# design.net
KiCad netlist of a schematic drawn in Altium Designer
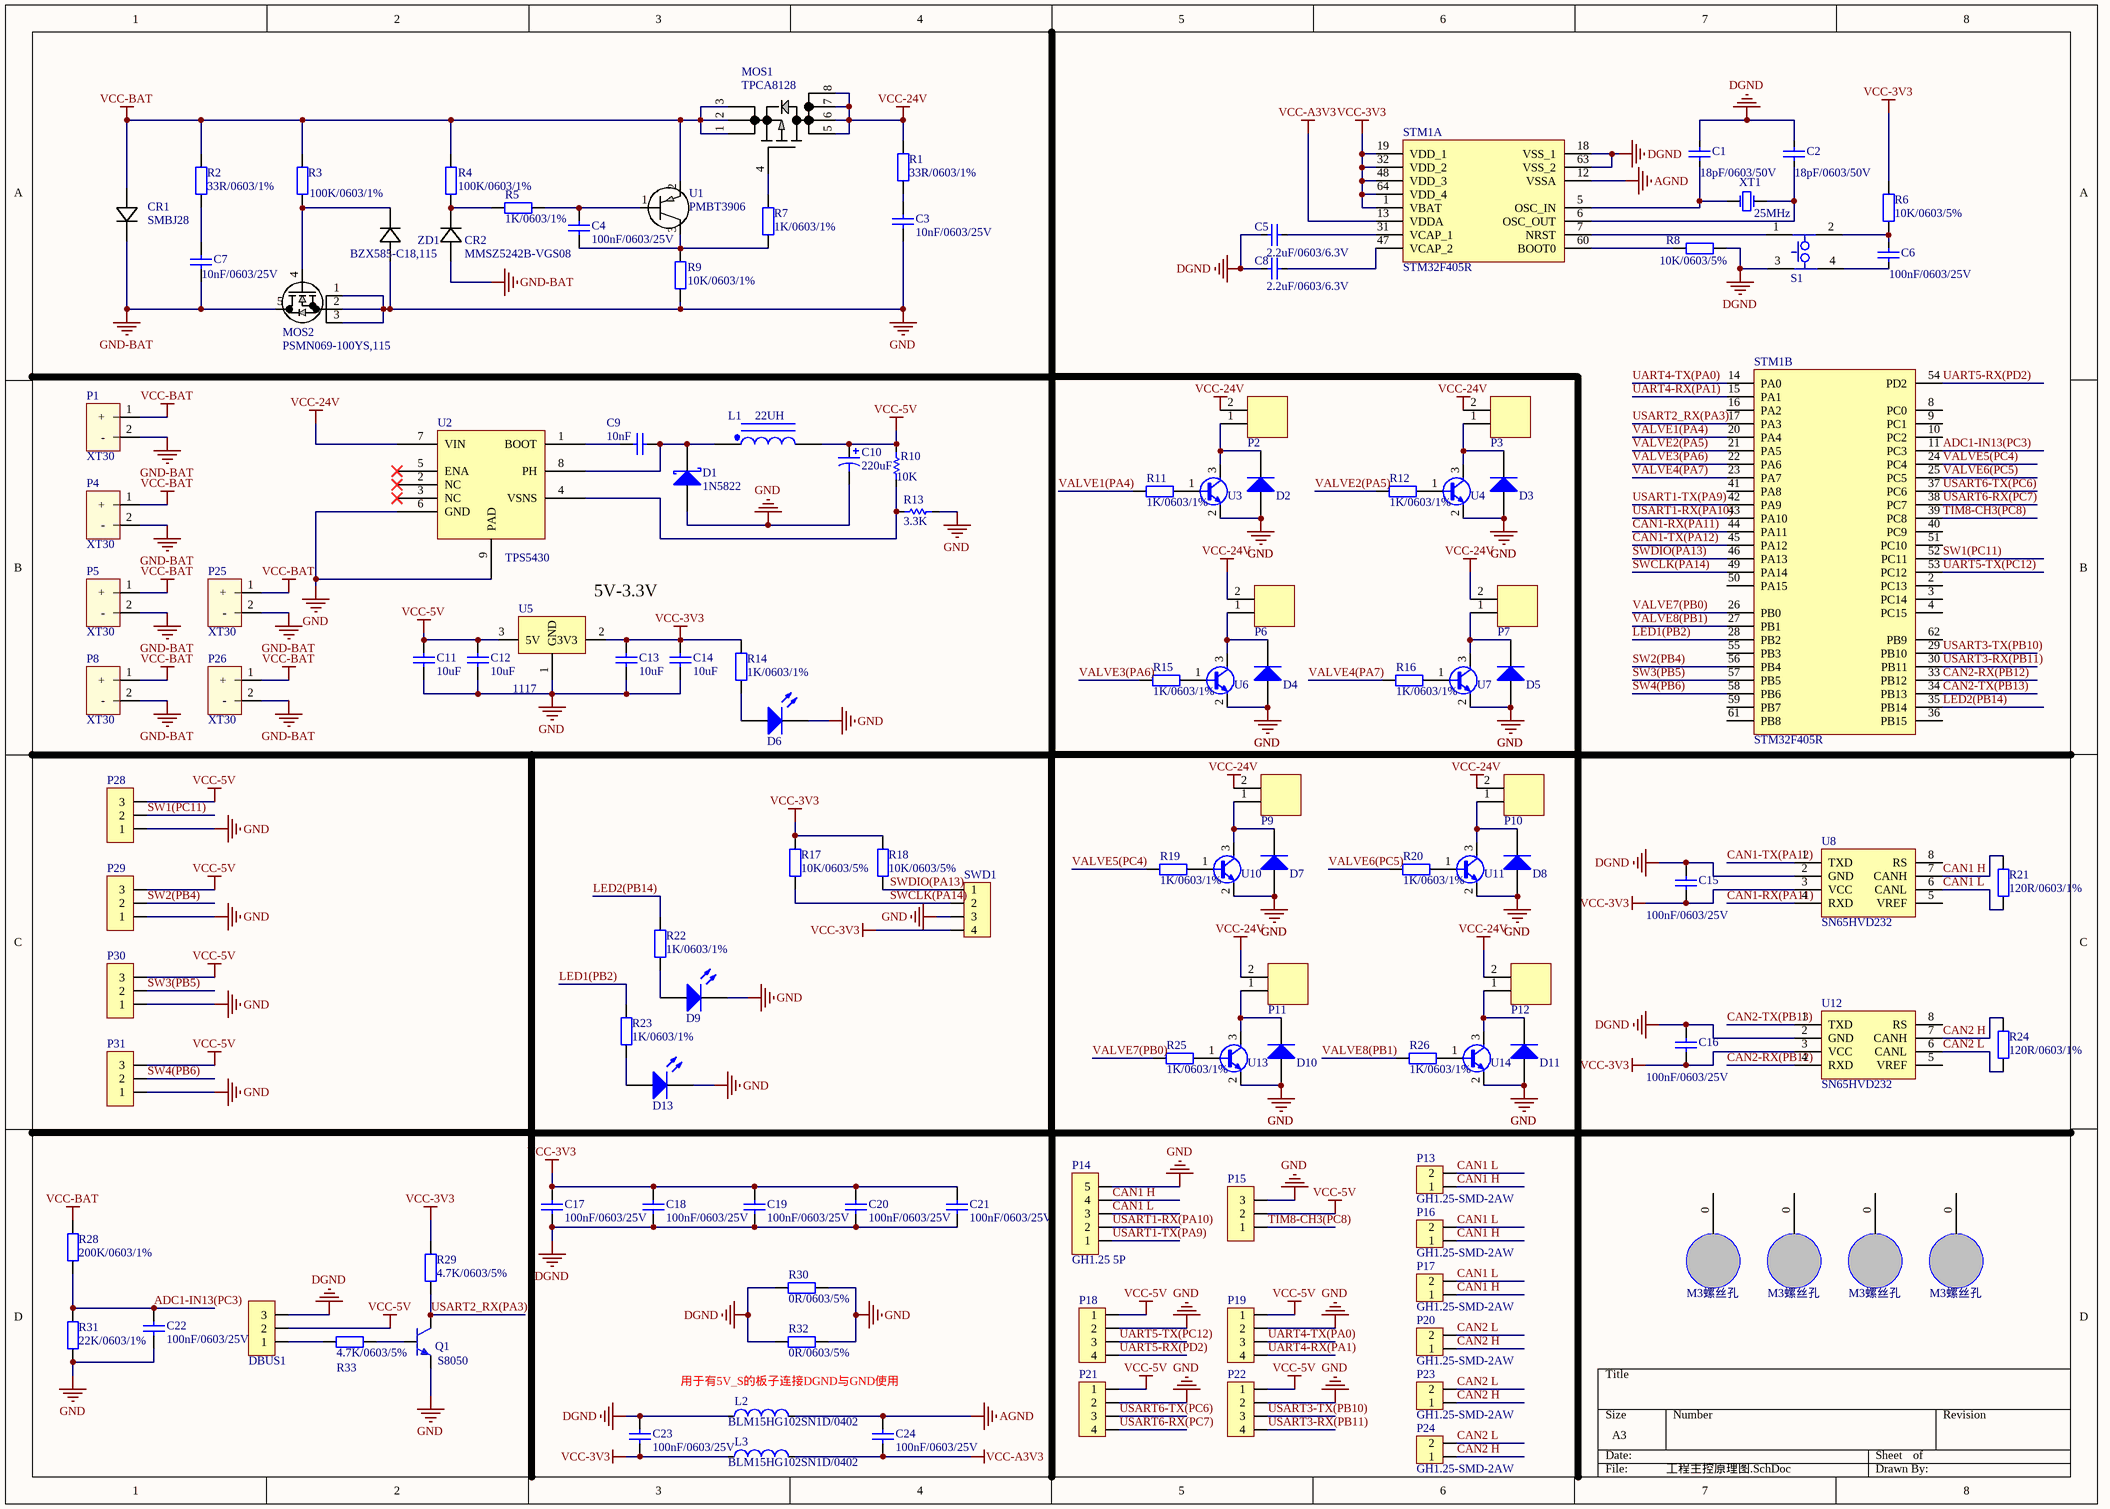
[diagram p0: 工程主控原理图.SchDoc]

(export (version "E")
  (design (tool "Eeschema 10.0.6"))
  (components
    (comp (ref "C1")
      (value "18pF/0603/50V")
      (footprint "C-SMD-0603")
      (description "Capacitor")
      (fields (field (name "Comment") "18pF"))
      (libsource (lib "SCH_Passive") (part "Cap_0402"))
    )
    (comp (ref "C2")
      (value "18pF/0603/50V")
      (footprint "C-SMD-0603")
      (description "Capacitor")
      (fields (field (name "Comment") "18pF"))
      (libsource (lib "SCH_Passive") (part "Cap_0402"))
    )
    (comp (ref "C3")
      (value "10nF/0603/25V")
      (footprint "C-SMD-0603")
      (description "贴片电容")
      (fields (field (name "Comment") "10nF") (field (name "PUBLISHER") "Altium Limited"))
      (libsource (lib "三代主控板原理图库") (part "Cap"))
    )
    (comp (ref "C4")
      (value "100nF/0603/25V")
      (footprint "C-SMD-0603")
      (description "贴片电容")
      (fields (field (name "Comment") "100nF") (field (name "PUBLISHER") "Altium Limited"))
      (libsource (lib "三代主控板原理图库") (part "Cap"))
    )
    (comp (ref "C5")
      (value "2.2uF/0603/6.3V")
      (footprint "C-SMD-0603")
      (description "Capacitor")
      (fields (field (name "Comment") "2.2uF"))
      (libsource (lib "SCH_Passive") (part "Cap_0402"))
    )
    (comp (ref "C6")
      (value "100nF/0603/25V")
      (footprint "C-SMD-0603")
      (description "Capacitor")
      (fields (field (name "Comment") "100nF"))
      (libsource (lib "SCH_Passive") (part "Cap_0402"))
    )
    (comp (ref "C7")
      (value "10nF/0603/25V")
      (footprint "C-SMD-0603")
      (description "贴片电容")
      (fields (field (name "Comment") "10nF") (field (name "PUBLISHER") "Altium Limited"))
      (libsource (lib "三代主控板原理图库") (part "Cap"))
    )
    (comp (ref "C8")
      (value "2.2uF/0603/6.3V")
      (footprint "C-SMD-0603")
      (description "Capacitor")
      (fields (field (name "Comment") "2.2uF"))
      (libsource (lib "SCH_Passive") (part "Cap_0402"))
    )
    (comp (ref "C9")
      (value "10nF")
      (footprint "C-SMD-0603")
      (description "无极性电容")
      (fields (field (name "PUBLISHER") "Altium Limited"))
      (libsource (lib "Devices") (part "Cap"))
    )
    (comp (ref "C10")
      (value "220uF")
      (footprint "TCAP7343")
      (description "Polarized Capacitor (Radial)")
      (fields (field (name "PUBLISHER") "Altium Limited"))
      (libsource (lib "Miscellaneous Devices") (part "Cap Pol1"))
    )
    (comp (ref "C11")
      (value "10uF")
      (footprint "C-SMD-0603")
      (description "无极性电容")
      (fields (field (name "PUBLISHER") "Altium Limited"))
      (libsource (lib "Devices") (part "Cap"))
    )
    (comp (ref "C12")
      (value "10uF")
      (footprint "C-SMD-0603")
      (description "无极性电容")
      (fields (field (name "PUBLISHER") "Altium Limited"))
      (libsource (lib "Devices") (part "Cap"))
    )
    (comp (ref "C13")
      (value "10uF")
      (footprint "C-SMD-0603")
      (description "无极性电容")
      (fields (field (name "PUBLISHER") "Altium Limited"))
      (libsource (lib "Devices") (part "Cap"))
    )
    (comp (ref "C14")
      (value "10uF")
      (footprint "C-SMD-0603")
      (description "无极性电容")
      (fields (field (name "PUBLISHER") "Altium Limited"))
      (libsource (lib "Devices") (part "Cap"))
    )
    (comp (ref "C15")
      (value "100nF/0603/25V")
      (footprint "C-SMD-0603")
      (description "贴片电容")
      (fields (field (name "Comment") "100NF") (field (name "PUBLISHER") "Altium Limited"))
      (libsource (lib "三代主控板原理图库") (part "Cap"))
    )
    (comp (ref "C16")
      (value "100nF/0603/25V")
      (footprint "C-SMD-0603")
      (description "贴片电容")
      (fields (field (name "Comment") "100NF") (field (name "PUBLISHER") "Altium Limited"))
      (libsource (lib "三代主控板原理图库") (part "Cap"))
    )
    (comp (ref "C17")
      (value "100nF/0603/25V")
      (footprint "C-SMD-0603")
      (description "贴片电容")
      (fields (field (name "Comment") "100nF") (field (name "PUBLISHER") "Altium Limited"))
      (libsource (lib "三代主控板原理图库") (part "Cap"))
    )
    (comp (ref "C18")
      (value "100nF/0603/25V")
      (footprint "C-SMD-0603")
      (description "贴片电容")
      (fields (field (name "Comment") "100nF") (field (name "PUBLISHER") "Altium Limited"))
      (libsource (lib "三代主控板原理图库") (part "Cap"))
    )
    (comp (ref "C19")
      (value "100nF/0603/25V")
      (footprint "C-SMD-0603")
      (description "贴片电容")
      (fields (field (name "Comment") "100nF") (field (name "PUBLISHER") "Altium Limited"))
      (libsource (lib "三代主控板原理图库") (part "Cap"))
    )
    (comp (ref "C20")
      (value "100nF/0603/25V")
      (footprint "C-SMD-0603")
      (description "贴片电容")
      (fields (field (name "Comment") "100nF") (field (name "PUBLISHER") "Altium Limited"))
      (libsource (lib "三代主控板原理图库") (part "Cap"))
    )
    (comp (ref "C21")
      (value "100nF/0603/25V")
      (footprint "C-SMD-0603")
      (description "贴片电容")
      (fields (field (name "Comment") "100nF") (field (name "PUBLISHER") "Altium Limited"))
      (libsource (lib "三代主控板原理图库") (part "Cap"))
    )
    (comp (ref "C22")
      (value "100nF/0603/25V")
      (footprint "C-SMD-0603")
      (description "贴片电容")
      (fields (field (name "Comment") "100nF") (field (name "PUBLISHER") "Altium Limited"))
      (libsource (lib "三代主控板原理图库") (part "Cap"))
    )
    (comp (ref "C23")
      (value "100nF/0603/25V")
      (footprint "C-SMD-0603")
      (description "贴片电容")
      (fields (field (name "Comment") "100nF") (field (name "PUBLISHER") "Altium Limited"))
      (libsource (lib "三代主控板原理图库") (part "Cap"))
    )
    (comp (ref "C24")
      (value "100nF/0603/25V")
      (footprint "C-SMD-0603")
      (description "贴片电容")
      (fields (field (name "Comment") "100nF") (field (name "PUBLISHER") "Altium Limited"))
      (libsource (lib "三代主控板原理图库") (part "Cap"))
    )
    (comp (ref "CR1")
      (value "SMBJ28")
      (footprint "SMBJSeries_LTF")
      (description "No Description Available")
      (fields
        (field (name "MANUFACTURER_PART_NUMBER") "SMBJ10")
        (field (name "COPYRIGHT") "Copyright (C) 2018 Accelerated Designs. All rights reserved")
      )
      (libsource (lib "SMBJ") (part "SMBJ10"))
    )
    (comp (ref "CR2")
      (value "MMSZ5242B-VGS08")
      (footprint "SOD123_MMS")
      (description "No Description Available")
      (fields (field (name "COPYRIGHT") "Copyright (C) 2018 Accelerated Designs. All rights reserved"))
      (libsource (lib "mmsz") (part "MMSZ5242B-VGS08"))
    )
    (comp (ref "D1")
      (value "1N5822")
      (footprint "SS34")
      (description "Schottky Diode")
      (fields (field (name "PUBLISHER") "Altium Limited"))
      (libsource (lib "Miscellaneous Devices") (part "D Schottky"))
    )
    (comp (ref "D2")
      (value "Diode_SS34")
      (footprint "SS34")
      (description "肖特基二极管")
      (libsource (lib "SHAWN") (part "Diode_SS34"))
    )
    (comp (ref "D3")
      (value "Diode_SS34")
      (footprint "SS34")
      (description "肖特基二极管")
      (libsource (lib "SHAWN") (part "Diode_SS34"))
    )
    (comp (ref "D4")
      (value "Diode_SS34")
      (footprint "SS34")
      (description "肖特基二极管")
      (libsource (lib "SHAWN") (part "Diode_SS34"))
    )
    (comp (ref "D5")
      (value "Diode_SS34")
      (footprint "SS34")
      (description "肖特基二极管")
      (libsource (lib "SHAWN") (part "Diode_SS34"))
    )
    (comp (ref "D6")
      (value "LED0")
      (footprint "LED-0603")
      (description "发光二极管")
      (fields (field (name "PUBLISHER") "Altium Limited"))
      (libsource (lib "Devices") (part "LED0"))
    )
    (comp (ref "D7")
      (value "Diode_SS34")
      (footprint "SS34")
      (description "肖特基二极管")
      (libsource (lib "SHAWN") (part "Diode_SS34"))
    )
    (comp (ref "D8")
      (value "Diode_SS34")
      (footprint "SS34")
      (description "肖特基二极管")
      (libsource (lib "SHAWN") (part "Diode_SS34"))
    )
    (comp (ref "D9")
      (value "LED0")
      (footprint "LED-0603")
      (description "发光二极管")
      (fields (field (name "PUBLISHER") "Altium Limited"))
      (libsource (lib "Devices") (part "LED0"))
    )
    (comp (ref "D10")
      (value "Diode_SS34")
      (footprint "SS34")
      (description "肖特基二极管")
      (libsource (lib "SHAWN") (part "Diode_SS34"))
    )
    (comp (ref "D11")
      (value "Diode_SS34")
      (footprint "SS34")
      (description "肖特基二极管")
      (libsource (lib "SHAWN") (part "Diode_SS34"))
    )
    (comp (ref "D13")
      (value "LED0")
      (footprint "LED-0603")
      (description "发光二极管")
      (fields (field (name "PUBLISHER") "Altium Limited"))
      (libsource (lib "Devices") (part "LED0"))
    )
    (comp (ref "DBUS1")
      (value "Header 3")
      (footprint "HDR1x3")
      (description "Header")
      (fields (field (name "PUBLISHER") "Altium Limited"))
      (libsource (lib "排针排母") (part "Header 3"))
    )
    (comp (ref "L1")
      (value "22UH")
      (footprint "L-7070")
      (description "Magnetic-Core Inductor with Winding Polarity Marking")
      (fields (field (name "PUBLISHER") "Altium Limited"))
      (libsource (lib "Miscellaneous Devices") (part "Inductor Iron Dot"))
    )
    (comp (ref "L2")
      (value "BLM15HG102SN1D/0402")
      (footprint "l-SMD-0402")
      (description "Inductor")
      (fields (field (name "Comment") "BLM15HG102SN1D"))
      (libsource (lib "三代主控板原理图库") (part "BLM15HG102SN1D/0402"))
    )
    (comp (ref "L3")
      (value "BLM15HG102SN1D/0402")
      (footprint "l-SMD-0402")
      (description "Inductor")
      (fields (field (name "Comment") "BLM15HG102SN1D"))
      (libsource (lib "三代主控板原理图库") (part "BLM15HG102SN1D/0402"))
    )
    (comp (ref "M1") (value "M3螺丝孔") (footprint "M3螺丝") (libsource (lib "My_SCHLib") (part "M3螺丝孔")))
    (comp (ref "M2") (value "M3螺丝孔") (footprint "M3螺丝") (libsource (lib "My_SCHLib") (part "M3螺丝孔")))
    (comp (ref "M3") (value "M3螺丝孔") (footprint "M3螺丝") (libsource (lib "My_SCHLib") (part "M3螺丝孔")))
    (comp (ref "M4") (value "M3螺丝孔") (footprint "M3螺丝") (libsource (lib "My_SCHLib") (part "M3螺丝孔")))
    (comp (ref "MOS1")
      (value "TPCA8128")
      (footprint "SOP Advance_TOS")
      (description "No Description Available")
      (fields (field (name "COPYRIGHT") "Copyright (C) 2018 Accelerated Designs. All rights reserved"))
      (libsource (lib "TPCA8122") (part "TPCA8128"))
    )
    (comp (ref "MOS2")
      (value "PSMN069-100YS,115")
      (footprint "LFPAK56_POWER-SO8_SOT669_NEX")
      (description "No Description Available")
      (fields (field (name "COPYRIGHT") "Copyright (C) 2018 Accelerated Designs. All rights reserved"))
      (libsource (lib "psmn") (part "PSMN069-100YS,115"))
    )
    (comp (ref "P1")
      (value "XT30")
      (footprint "XT30-F")
      (description "2P电源连接器母座")
      (libsource (lib "机器人队F405新主控1") (part "XT30-F"))
    )
    (comp (ref "P2") (value "Header") (footprint "PH2.0-2P") (libsource (lib "SHAWN") (part "Header2")))
    (comp (ref "P3") (value "Header") (footprint "PH2.0-2P") (libsource (lib "SHAWN") (part "Header2")))
    (comp (ref "P4")
      (value "XT30")
      (footprint "XT30-F")
      (description "2P电源连接器母座")
      (libsource (lib "机器人队F405新主控1") (part "XT30-F"))
    )
    (comp (ref "P5")
      (value "XT30")
      (footprint "XT30-F")
      (description "2P电源连接器母座")
      (libsource (lib "机器人队F405新主控1") (part "XT30-F"))
    )
    (comp (ref "P6") (value "Header") (footprint "PH2.0-2P") (libsource (lib "SHAWN") (part "Header2")))
    (comp (ref "P7") (value "Header") (footprint "PH2.0-2P") (libsource (lib "SHAWN") (part "Header2")))
    (comp (ref "P8")
      (value "XT30")
      (footprint "XT30-F")
      (description "2P电源连接器母座")
      (libsource (lib "机器人队F405新主控1") (part "XT30-F"))
    )
    (comp (ref "P9") (value "Header") (footprint "PH2.0-2P") (libsource (lib "SHAWN") (part "Header2")))
    (comp (ref "P10") (value "Header") (footprint "PH2.0-2P") (libsource (lib "SHAWN") (part "Header2")))
    (comp (ref "P11") (value "Header") (footprint "PH2.0-2P") (libsource (lib "SHAWN") (part "Header2")))
    (comp (ref "P12") (value "Header") (footprint "PH2.0-2P") (libsource (lib "SHAWN") (part "Header2")))
    (comp (ref "P13")
      (value "GH1.25-SMD-2AW")
      (footprint "GH1.25-SMD-2AW")
      (description "pitch 1.25mm，2P，公座（A代表公，Y代表母），卧贴")
      (libsource (lib "SCH_Connector") (part "GH1.25-SMD-2AW"))
    )
    (comp (ref "P14")
      (value "GH1.25 5P")
      (footprint "GH1.25-SMD-5AW")
      (libsource (lib "gh1.25 5p") (part "GH1.25 5P"))
    )
    (comp (ref "P15")
      (value "Header 3")
      (footprint "HDR1X3")
      (description "Header")
      (fields (field (name "PUBLISHER") "Altium Limited"))
      (libsource (lib "排针排母") (part "Header 3"))
    )
    (comp (ref "P16")
      (value "GH1.25-SMD-2AW")
      (footprint "GH1.25-SMD-2AW")
      (description "pitch 1.25mm，2P，公座（A代表公，Y代表母），卧贴")
      (libsource (lib "SCH_Connector") (part "GH1.25-SMD-2AW"))
    )
    (comp (ref "P17")
      (value "GH1.25-SMD-2AW")
      (footprint "GH1.25-SMD-2AW")
      (description "pitch 1.25mm，2P，公座（A代表公，Y代表母），卧贴")
      (libsource (lib "SCH_Connector") (part "GH1.25-SMD-2AW"))
    )
    (comp (ref "P18")
      (value "GH1.25-SMD-4AW")
      (footprint "GH1.25-SMD-4AW")
      (description "pitch 1.25mm，4P，公座（A代表公，Y代表母），卧贴")
      (libsource (lib "SCH_Connector") (part "GH1.25-SMD-4AW"))
    )
    (comp (ref "P19")
      (value "GH1.25-SMD-4AW")
      (footprint "GH1.25-SMD-4AW")
      (description "pitch 1.25mm，4P，公座（A代表公，Y代表母），卧贴")
      (libsource (lib "SCH_Connector") (part "GH1.25-SMD-4AW"))
    )
    (comp (ref "P20")
      (value "GH1.25-SMD-2AW")
      (footprint "GH1.25-SMD-2AW")
      (description "pitch 1.25mm，2P，公座（A代表公，Y代表母），卧贴")
      (libsource (lib "SCH_Connector") (part "GH1.25-SMD-2AW"))
    )
    (comp (ref "P21")
      (value "GH1.25-SMD-4AW")
      (footprint "GH1.25-SMD-4AW")
      (description "pitch 1.25mm，4P，公座（A代表公，Y代表母），卧贴")
      (libsource (lib "SCH_Connector") (part "GH1.25-SMD-4AW"))
    )
    (comp (ref "P22")
      (value "GH1.25-SMD-4AW")
      (footprint "GH1.25-SMD-4AW")
      (description "pitch 1.25mm，4P，公座（A代表公，Y代表母），卧贴")
      (libsource (lib "SCH_Connector") (part "GH1.25-SMD-4AW"))
    )
    (comp (ref "P23")
      (value "GH1.25-SMD-2AW")
      (footprint "GH1.25-SMD-2AW")
      (description "pitch 1.25mm，2P，公座（A代表公，Y代表母），卧贴")
      (libsource (lib "SCH_Connector") (part "GH1.25-SMD-2AW"))
    )
    (comp (ref "P24")
      (value "GH1.25-SMD-2AW")
      (footprint "GH1.25-SMD-2AW")
      (description "pitch 1.25mm，2P，公座（A代表公，Y代表母），卧贴")
      (libsource (lib "SCH_Connector") (part "GH1.25-SMD-2AW"))
    )
    (comp (ref "P25")
      (value "XT30")
      (footprint "XT30-F")
      (description "2P电源连接器母座")
      (libsource (lib "机器人队F405新主控1") (part "XT30-F"))
    )
    (comp (ref "P26")
      (value "XT30")
      (footprint "XT30-F")
      (description "2P电源连接器母座")
      (libsource (lib "机器人队F405新主控1") (part "XT30-F"))
    )
    (comp (ref "P28")
      (value "Header 3")
      (footprint "GH1.25-SMD-3AW")
      (description "Header")
      (fields (field (name "PUBLISHER") "Altium Limited"))
      (libsource (lib "排针排母") (part "Header 3"))
    )
    (comp (ref "P29")
      (value "Header 3")
      (footprint "GH1.25-SMD-3AW")
      (description "Header")
      (fields (field (name "PUBLISHER") "Altium Limited"))
      (libsource (lib "排针排母") (part "Header 3"))
    )
    (comp (ref "P30")
      (value "Header 3")
      (footprint "GH1.25-SMD-3AW")
      (description "Header")
      (fields (field (name "PUBLISHER") "Altium Limited"))
      (libsource (lib "排针排母") (part "Header 3"))
    )
    (comp (ref "P31")
      (value "Header 3")
      (footprint "GH1.25-SMD-3AW")
      (description "Header")
      (fields (field (name "PUBLISHER") "Altium Limited"))
      (libsource (lib "排针排母") (part "Header 3"))
    )
    (comp (ref "Q1")
      (value "S8050")
      (footprint "SOT23-3")
      (description "Transistor")
      (libsource (lib "SCH_Active") (part "BJT_NPN"))
    )
    (comp (ref "R1")
      (value "33R/0603/1%")
      (footprint "R-SMD-0603")
      (description "贴片电阻")
      (fields (field (name "Comment") "33R") (field (name "PUBLISHER") "Altium Limited"))
      (libsource (lib "") (part "Res1_1"))
    )
    (comp (ref "R2")
      (value "33R/0603/1%")
      (footprint "R-SMD-0603")
      (description "贴片电阻")
      (fields (field (name "Comment") "33R") (field (name "PUBLISHER") "Altium Limited"))
      (libsource (lib "") (part "Res1_1"))
    )
    (comp (ref "R3")
      (value "100K/0603/1%")
      (footprint "R-SMD-0603")
      (description "贴片电阻")
      (fields (field (name "Comment") "100K") (field (name "PUBLISHER") "Altium Limited"))
      (libsource (lib "") (part "Res1_1"))
    )
    (comp (ref "R4")
      (value "100K/0603/1%")
      (footprint "R-SMD-0603")
      (description "贴片电阻")
      (fields (field (name "Comment") "100K") (field (name "PUBLISHER") "Altium Limited"))
      (libsource (lib "") (part "Res1_1"))
    )
    (comp (ref "R5")
      (value "1K/0603/1%")
      (footprint "R-SMD-0603")
      (description "贴片电阻")
      (fields (field (name "Comment") "1K") (field (name "PUBLISHER") "Altium Limited"))
      (libsource (lib "") (part "Res1_2"))
    )
    (comp (ref "R6")
      (value "10K/0603/5%")
      (footprint "R-SMD-0603")
      (description "Resistor")
      (fields (field (name "Comment") "10K"))
      (libsource (lib "") (part "Res_0402_2"))
    )
    (comp (ref "R7")
      (value "1K/0603/1%")
      (footprint "R-SMD-0603")
      (description "贴片电阻")
      (fields (field (name "Comment") "1K") (field (name "PUBLISHER") "Altium Limited"))
      (libsource (lib "底盘主控") (part "Res1"))
    )
    (comp (ref "R8")
      (value "10K/0603/5%")
      (footprint "R-SMD-0603")
      (description "Resistor")
      (fields (field (name "Comment") "10K"))
      (libsource (lib "") (part "Res_0402_1"))
    )
    (comp (ref "R9")
      (value "10K/0603/1%")
      (footprint "R-SMD-0603")
      (description "贴片电阻")
      (fields (field (name "Comment") "10K") (field (name "PUBLISHER") "Altium Limited"))
      (libsource (lib "") (part "Res1_1"))
    )
    (comp (ref "R10")
      (value "10K")
      (footprint "R-SMD-0603")
      (description "贴片电阻")
      (fields (field (name "PUBLISHER") "Altium Limited"))
      (libsource (lib "Devices") (part "Res1"))
    )
    (comp (ref "R11")
      (value "1K/0603/1%")
      (footprint "R-SMD-0603")
      (description "贴片电阻")
      (fields (field (name "Comment") "1K"))
      (libsource (lib "三代主控板原理图库") (part "Res"))
    )
    (comp (ref "R12")
      (value "1K/0603/1%")
      (footprint "R-SMD-0603")
      (description "贴片电阻")
      (fields (field (name "Comment") "1K"))
      (libsource (lib "三代主控板原理图库") (part "Res"))
    )
    (comp (ref "R13")
      (value "3.3K")
      (footprint "R-SMD-0603")
      (description "贴片电阻")
      (fields (field (name "PUBLISHER") "Altium Limited"))
      (libsource (lib "Devices") (part "Res1"))
    )
    (comp (ref "R14")
      (value "1K/0603/1%")
      (footprint "R-SMD-0603")
      (description "贴片电阻")
      (fields (field (name "Comment") "1K") (field (name "PUBLISHER") "Altium Limited"))
      (libsource (lib "") (part "Res1_1"))
    )
    (comp (ref "R15")
      (value "1K/0603/1%")
      (footprint "R-SMD-0603")
      (description "贴片电阻")
      (fields (field (name "Comment") "1K"))
      (libsource (lib "三代主控板原理图库") (part "Res"))
    )
    (comp (ref "R16")
      (value "1K/0603/1%")
      (footprint "R-SMD-0603")
      (description "贴片电阻")
      (fields (field (name "Comment") "1K"))
      (libsource (lib "三代主控板原理图库") (part "Res"))
    )
    (comp (ref "R17")
      (value "10K/0603/5%")
      (footprint "R-SMD-0603")
      (description "Resistor")
      (fields (field (name "Comment") "10K"))
      (libsource (lib "SCH_Passive") (part "Res_0402"))
    )
    (comp (ref "R18")
      (value "10K/0603/5%")
      (footprint "R-SMD-0603")
      (description "Resistor")
      (fields (field (name "Comment") "10K"))
      (libsource (lib "SCH_Passive") (part "Res_0402"))
    )
    (comp (ref "R19")
      (value "1K/0603/1%")
      (footprint "R-SMD-0603")
      (description "贴片电阻")
      (fields (field (name "Comment") "1K"))
      (libsource (lib "三代主控板原理图库") (part "Res"))
    )
    (comp (ref "R20")
      (value "1K/0603/1%")
      (footprint "R-SMD-0603")
      (description "贴片电阻")
      (fields (field (name "Comment") "1K"))
      (libsource (lib "三代主控板原理图库") (part "Res"))
    )
    (comp (ref "R21")
      (value "120R/0603/1%")
      (footprint "R-SMD-0603")
      (description "贴片电阻")
      (fields (field (name "Comment") "120R"))
      (libsource (lib "") (part "Res_1"))
    )
    (comp (ref "R22")
      (value "1K/0603/1%")
      (footprint "R-SMD-0603")
      (description "贴片电阻")
      (fields (field (name "Comment") "1K") (field (name "PUBLISHER") "Altium Limited"))
      (libsource (lib "") (part "Res1_1"))
    )
    (comp (ref "R23")
      (value "1K/0603/1%")
      (footprint "R-SMD-0603")
      (description "贴片电阻")
      (fields (field (name "Comment") "1K") (field (name "PUBLISHER") "Altium Limited"))
      (libsource (lib "") (part "Res1_1"))
    )
    (comp (ref "R24")
      (value "120R/0603/1%")
      (footprint "R-SMD-0603")
      (description "贴片电阻")
      (fields (field (name "Comment") "120R"))
      (libsource (lib "") (part "Res_1"))
    )
    (comp (ref "R25")
      (value "1K/0603/1%")
      (footprint "R-SMD-0603")
      (description "贴片电阻")
      (fields (field (name "Comment") "1K"))
      (libsource (lib "三代主控板原理图库") (part "Res"))
    )
    (comp (ref "R26")
      (value "1K/0603/1%")
      (footprint "R-SMD-0603")
      (description "贴片电阻")
      (fields (field (name "Comment") "1K"))
      (libsource (lib "三代主控板原理图库") (part "Res"))
    )
    (comp (ref "R28")
      (value "200K/0603/1%")
      (footprint "R-SMD-0603")
      (description "贴片电阻")
      (fields (field (name "Comment") "200K") (field (name "PUBLISHER") "Altium Limited"))
      (libsource (lib "底盘主控") (part "Res1"))
    )
    (comp (ref "R29")
      (value "4.7K/0603/5%")
      (footprint "R-SMD-0603")
      (description "Resistor")
      (fields (field (name "Comment") "4.7K"))
      (libsource (lib "SCH_Passive") (part "Res_0603"))
    )
    (comp (ref "R30")
      (value "0R/0603/5%")
      (footprint "R-SMD-0603")
      (description "Resistor")
      (fields (field (name "Comment") "0R"))
      (libsource (lib "电容电阻电感") (part "Res_0603"))
    )
    (comp (ref "R31")
      (value "22K/0603/1%")
      (footprint "R-SMD-0603")
      (description "贴片电阻")
      (fields (field (name "Comment") "22K") (field (name "PUBLISHER") "Altium Limited"))
      (libsource (lib "底盘主控") (part "Res1"))
    )
    (comp (ref "R32")
      (value "0R/0603/5%")
      (footprint "R-SMD-0603")
      (description "Resistor")
      (fields (field (name "Comment") "0R"))
      (libsource (lib "电容电阻电感") (part "Res_0603"))
    )
    (comp (ref "R33")
      (value "4.7K/0603/5%")
      (footprint "R-SMD-0603")
      (description "Resistor")
      (fields (field (name "Comment") "4.7K"))
      (libsource (lib "") (part "Res_0603_1"))
    )
    (comp (ref "S1")
      (value "SKRPADE010")
      (footprint "SKRPADE010")
      (description "Switch")
      (fields (field (name "PUBLISHER") "Altium Limited"))
      (libsource (lib "SCH_Switch") (part "SKRPADE010"))
    )
    (comp (ref "STM1")
      (value "STM32F405R")
      (footprint "LQFP64")
      (description "MCU")
      (libsource (lib "SCH_IC") (part "STM32F405R"))
    )
    (comp (ref "SWD1")
      (value "GH1.25-SMD-4AW")
      (footprint "molex1.25-4p")
      (description "pitch 1.25mm，4P，公座（A代表公，Y代表母），卧贴")
      (libsource (lib "") (part "GH1.25-SMD-4AW_1"))
    )
    (comp (ref "U1")
      (value "PMBT3906")
      (footprint "SOT23_NEX")
      (description "No Description Available")
      (fields (field (name "COPYRIGHT") "Copyright (C) 2016 Accelerated Designs. All rights reserved"))
      (libsource (lib "PBMT3906") (part "PMBT3906"))
    )
    (comp (ref "U2") (value "TPS5430") (footprint "TPS5430") (libsource (lib "Schlib1") (part "TPS5430")))
    (comp (ref "U3") (value "BJT-2N5551") (footprint "SOT23-3") (libsource (lib "SHAWN") (part "BJT-2N5551")))
    (comp (ref "U4") (value "BJT-2N5551") (footprint "SOT23-3") (libsource (lib "SHAWN") (part "BJT-2N5551")))
    (comp (ref "U5") (value "1117") (footprint "AMS1117") (libsource (lib "SHAWN") (part "AMS1117-3.3")))
    (comp (ref "U6") (value "BJT-2N5551") (footprint "SOT23-3") (libsource (lib "SHAWN") (part "BJT-2N5551")))
    (comp (ref "U7") (value "BJT-2N5551") (footprint "SOT23-3") (libsource (lib "SHAWN") (part "BJT-2N5551")))
    (comp (ref "U8")
      (value "SN65HVD232")
      (footprint "SOP-8")
      (description "CAN")
      (libsource (lib "SCH_IC") (part "SN65HVD232"))
    )
    (comp (ref "U10")
      (value "BJT-2N5551")
      (footprint "SOT23-3")
      (libsource (lib "SHAWN") (part "BJT-2N5551"))
    )
    (comp (ref "U11")
      (value "BJT-2N5551")
      (footprint "SOT23-3")
      (libsource (lib "SHAWN") (part "BJT-2N5551"))
    )
    (comp (ref "U12")
      (value "SN65HVD232")
      (footprint "SOP-8")
      (description "CAN")
      (libsource (lib "SCH_IC") (part "SN65HVD232"))
    )
    (comp (ref "U13")
      (value "BJT-2N5551")
      (footprint "SOT23-3")
      (libsource (lib "SHAWN") (part "BJT-2N5551"))
    )
    (comp (ref "U14")
      (value "BJT-2N5551")
      (footprint "SOT23-3")
      (libsource (lib "SHAWN") (part "BJT-2N5551"))
    )
    (comp (ref "XT1")
      (value "25MHz")
      (footprint "XTAL3225")
      (description "Crystal Oscillator")
      (fields (field (name "PUBLISHER") "Altium Limited"))
      (libsource (lib "SCH_Oscillator") (part "XTAL_5032"))
    )
    (comp (ref "ZD1")
      (value "BZX585-C18,115")
      (footprint "CR_85-C18,115_NEX")
      (description "No Description Available")
      (fields (field (name "COPYRIGHT") "Copyright (C) 2018 Accelerated Designs. All rights reserved"))
      (libsource (lib "bzx58") (part "BZX585-C18,115"))
    )
  )
  (nets
    (net (code "1") (name "/ADC1-IN13(PC3)") (class "Default")
      (node (ref "C22") (pin "2") (pinfunction "2_2") (pintype "passive"))
      (node (ref "R28") (pin "1") (pinfunction "1_1") (pintype "passive"))
      (node (ref "R31") (pin "2") (pinfunction "2_2") (pintype "passive"))
      (node (ref "STM1") (pin "11") (pinfunction "PC3_11") (pintype "passive"))
    )
    (net (code "2") (name "/CAN1 H") (class "Default")
      (node (ref "P13") (pin "1") (pinfunction "1_1") (pintype "passive"))
      (node (ref "P14") (pin "4") (pinfunction "4_4") (pintype "passive"))
      (node (ref "P16") (pin "1") (pinfunction "1_1") (pintype "passive"))
      (node (ref "P17") (pin "1") (pinfunction "1_1") (pintype "passive"))
      (node (ref "R21") (pin "2") (pinfunction "2_2") (pintype "passive"))
      (node (ref "U8") (pin "7") (pinfunction "CANH_7") (pintype "passive"))
    )
    (net (code "3") (name "/CAN1 L") (class "Default")
      (node (ref "P13") (pin "2") (pinfunction "2_2") (pintype "passive"))
      (node (ref "P14") (pin "3") (pinfunction "3_3") (pintype "passive"))
      (node (ref "P16") (pin "2") (pinfunction "2_2") (pintype "passive"))
      (node (ref "P17") (pin "2") (pinfunction "2_2") (pintype "passive"))
      (node (ref "R21") (pin "1") (pinfunction "1_1") (pintype "passive"))
      (node (ref "U8") (pin "6") (pinfunction "CANL_6") (pintype "passive"))
    )
    (net (code "4") (name "/CAN1-RX(PA11)") (class "Default")
      (node (ref "STM1") (pin "44") (pinfunction "PA11_44") (pintype "passive"))
      (node (ref "U8") (pin "4") (pinfunction "RXD_4") (pintype "passive"))
    )
    (net (code "5") (name "/CAN1-TX(PA12)") (class "Default")
      (node (ref "STM1") (pin "45") (pinfunction "PA12_45") (pintype "passive"))
      (node (ref "U8") (pin "1") (pinfunction "TXD_1") (pintype "passive"))
    )
    (net (code "6") (name "/CAN2 H") (class "Default")
      (node (ref "P20") (pin "1") (pinfunction "1_1") (pintype "passive"))
      (node (ref "P23") (pin "1") (pinfunction "1_1") (pintype "passive"))
      (node (ref "P24") (pin "1") (pinfunction "1_1") (pintype "passive"))
      (node (ref "R24") (pin "2") (pinfunction "2_2") (pintype "passive"))
      (node (ref "U12") (pin "7") (pinfunction "CANH_7") (pintype "passive"))
    )
    (net (code "7") (name "/CAN2 L") (class "Default")
      (node (ref "P20") (pin "2") (pinfunction "2_2") (pintype "passive"))
      (node (ref "P23") (pin "2") (pinfunction "2_2") (pintype "passive"))
      (node (ref "P24") (pin "2") (pinfunction "2_2") (pintype "passive"))
      (node (ref "R24") (pin "1") (pinfunction "1_1") (pintype "passive"))
      (node (ref "U12") (pin "6") (pinfunction "CANL_6") (pintype "passive"))
    )
    (net (code "8") (name "/CAN2-RX(PB12)") (class "Default")
      (node (ref "STM1") (pin "33") (pinfunction "PB12_33") (pintype "passive"))
      (node (ref "U12") (pin "4") (pinfunction "RXD_4") (pintype "passive"))
    )
    (net (code "9") (name "/CAN2-TX(PB13)") (class "Default")
      (node (ref "STM1") (pin "34") (pinfunction "PB13_34") (pintype "passive"))
      (node (ref "U12") (pin "1") (pinfunction "TXD_1") (pintype "passive"))
    )
    (net (code "10") (name "/LED1(PB2)") (class "Default")
      (node (ref "R23") (pin "1") (pinfunction "1_1") (pintype "passive"))
      (node (ref "STM1") (pin "28") (pinfunction "PB2_28") (pintype "passive"))
    )
    (net (code "11") (name "/LED2(PB14)") (class "Default")
      (node (ref "R22") (pin "1") (pinfunction "1_1") (pintype "passive"))
      (node (ref "STM1") (pin "35") (pinfunction "PB14_35") (pintype "passive"))
    )
    (net (code "12") (name "/SW1(PC11)") (class "Default")
      (node (ref "P28") (pin "2") (pinfunction "2_2") (pintype "passive"))
      (node (ref "STM1") (pin "52") (pinfunction "PC11_52") (pintype "passive"))
    )
    (net (code "13") (name "/SW2(PB4)") (class "Default")
      (node (ref "P29") (pin "2") (pinfunction "2_2") (pintype "passive"))
      (node (ref "STM1") (pin "56") (pinfunction "PB4_56") (pintype "passive"))
    )
    (net (code "14") (name "/SW3(PB5)") (class "Default")
      (node (ref "P30") (pin "2") (pinfunction "2_2") (pintype "passive"))
      (node (ref "STM1") (pin "57") (pinfunction "PB5_57") (pintype "passive"))
    )
    (net (code "15") (name "/SW4(PB6)") (class "Default")
      (node (ref "P31") (pin "2") (pinfunction "2_2") (pintype "passive"))
      (node (ref "STM1") (pin "58") (pinfunction "PB6_58") (pintype "passive"))
    )
    (net (code "16") (name "/SWCLK(PA14)") (class "Default")
      (node (ref "R17") (pin "2") (pinfunction "2_2") (pintype "passive"))
      (node (ref "STM1") (pin "49") (pinfunction "PA14_49") (pintype "passive"))
      (node (ref "SWD1") (pin "2") (pinfunction "2_2") (pintype "passive"))
    )
    (net (code "17") (name "/SWDIO(PA13)") (class "Default")
      (node (ref "R18") (pin "2") (pinfunction "2_2") (pintype "passive"))
      (node (ref "STM1") (pin "46") (pinfunction "PA13_46") (pintype "passive"))
      (node (ref "SWD1") (pin "1") (pinfunction "1_1") (pintype "passive"))
    )
    (net (code "18") (name "/TIM8-CH3(PC8)") (class "Default")
      (node (ref "P15") (pin "1") (pinfunction "1_1") (pintype "passive"))
      (node (ref "STM1") (pin "39") (pinfunction "PC8_39") (pintype "passive"))
    )
    (net (code "19") (name "/UART4-RX(PA1)") (class "Default")
      (node (ref "P19") (pin "4") (pinfunction "4_4") (pintype "passive"))
      (node (ref "STM1") (pin "15") (pinfunction "PA1_15") (pintype "passive"))
    )
    (net (code "20") (name "/UART4-TX(PA0)") (class "Default")
      (node (ref "P19") (pin "3") (pinfunction "3_3") (pintype "passive"))
      (node (ref "STM1") (pin "14") (pinfunction "PA0_14") (pintype "passive"))
    )
    (net (code "21") (name "/UART5-RX(PD2)") (class "Default")
      (node (ref "P18") (pin "4") (pinfunction "4_4") (pintype "passive"))
      (node (ref "STM1") (pin "54") (pinfunction "PD2_54") (pintype "passive"))
    )
    (net (code "22") (name "/UART5-TX(PC12)") (class "Default")
      (node (ref "P18") (pin "3") (pinfunction "3_3") (pintype "passive"))
      (node (ref "STM1") (pin "53") (pinfunction "PC12_53") (pintype "passive"))
    )
    (net (code "23") (name "/USART1-RX(PA10)") (class "Default")
      (node (ref "P14") (pin "2") (pinfunction "2_2") (pintype "passive"))
      (node (ref "STM1") (pin "43") (pinfunction "PA10_43") (pintype "passive"))
    )
    (net (code "24") (name "/USART1-TX(PA9)") (class "Default")
      (node (ref "P14") (pin "1") (pinfunction "1_1") (pintype "passive"))
      (node (ref "STM1") (pin "42") (pinfunction "PA9_42") (pintype "passive"))
    )
    (net (code "25") (name "/USART2_RX(PA3)") (class "Default")
      (node (ref "Q1") (pin "3") (pinfunction "C_3") (pintype "passive"))
      (node (ref "R29") (pin "2") (pinfunction "2_2") (pintype "passive"))
      (node (ref "STM1") (pin "17") (pinfunction "PA3_17") (pintype "passive"))
    )
    (net (code "26") (name "/USART3-RX(PB11)") (class "Default")
      (node (ref "P22") (pin "4") (pinfunction "4_4") (pintype "passive"))
      (node (ref "STM1") (pin "30") (pinfunction "PB11_30") (pintype "passive"))
    )
    (net (code "27") (name "/USART3-TX(PB10)") (class "Default")
      (node (ref "P22") (pin "3") (pinfunction "3_3") (pintype "passive"))
      (node (ref "STM1") (pin "29") (pinfunction "PB10_29") (pintype "passive"))
    )
    (net (code "28") (name "/USART6-RX(PC7)") (class "Default")
      (node (ref "P21") (pin "4") (pinfunction "4_4") (pintype "passive"))
      (node (ref "STM1") (pin "38") (pinfunction "PC7_38") (pintype "passive"))
    )
    (net (code "29") (name "/USART6-TX(PC6)") (class "Default")
      (node (ref "P21") (pin "3") (pinfunction "3_3") (pintype "passive"))
      (node (ref "STM1") (pin "37") (pinfunction "PC6_37") (pintype "passive"))
    )
    (net (code "30") (name "/VALVE1(PA4)") (class "Default")
      (node (ref "R11") (pin "1") (pinfunction "1_1") (pintype "passive"))
      (node (ref "STM1") (pin "20") (pinfunction "PA4_20") (pintype "passive"))
    )
    (net (code "31") (name "/VALVE2(PA5)") (class "Default")
      (node (ref "R12") (pin "1") (pinfunction "1_1") (pintype "passive"))
      (node (ref "STM1") (pin "21") (pinfunction "PA5_21") (pintype "passive"))
    )
    (net (code "32") (name "/VALVE3(PA6)") (class "Default")
      (node (ref "R15") (pin "1") (pinfunction "1_1") (pintype "passive"))
      (node (ref "STM1") (pin "22") (pinfunction "PA6_22") (pintype "passive"))
    )
    (net (code "33") (name "/VALVE4(PA7)") (class "Default")
      (node (ref "R16") (pin "1") (pinfunction "1_1") (pintype "passive"))
      (node (ref "STM1") (pin "23") (pinfunction "PA7_23") (pintype "passive"))
    )
    (net (code "34") (name "/VALVE5(PC4)") (class "Default")
      (node (ref "R19") (pin "1") (pinfunction "1_1") (pintype "passive"))
      (node (ref "STM1") (pin "24") (pinfunction "PC4_24") (pintype "passive"))
    )
    (net (code "35") (name "/VALVE6(PC5)") (class "Default")
      (node (ref "R20") (pin "1") (pinfunction "1_1") (pintype "passive"))
      (node (ref "STM1") (pin "25") (pinfunction "PC5_25") (pintype "passive"))
    )
    (net (code "36") (name "/VALVE7(PB0)") (class "Default")
      (node (ref "R25") (pin "1") (pinfunction "1_1") (pintype "passive"))
      (node (ref "STM1") (pin "26") (pinfunction "PB0_26") (pintype "passive"))
    )
    (net (code "37") (name "/VALVE8(PB1)") (class "Default")
      (node (ref "R26") (pin "1") (pinfunction "1_1") (pintype "passive"))
      (node (ref "STM1") (pin "27") (pinfunction "PB1_27") (pintype "passive"))
    )
    (net (code "38") (name "AGND") (class "Default")
      (node (ref "C24") (pin "2") (pinfunction "2_2") (pintype "passive"))
      (node (ref "L2") (pin "2") (pinfunction "2_2") (pintype "passive"))
      (node (ref "STM1") (pin "12") (pinfunction "VSSA_12") (pintype "passive"))
    )
    (net (code "39") (name "DGND") (class "Default")
      (node (ref "C1") (pin "2") (pinfunction "2_2") (pintype "passive"))
      (node (ref "C15") (pin "2") (pinfunction "2_2") (pintype "passive"))
      (node (ref "C16") (pin "2") (pinfunction "2_2") (pintype "passive"))
      (node (ref "C17") (pin "1") (pinfunction "1_1") (pintype "passive"))
      (node (ref "C18") (pin "1") (pinfunction "1_1") (pintype "passive"))
      (node (ref "C19") (pin "1") (pinfunction "1_1") (pintype "passive"))
      (node (ref "C2") (pin "2") (pinfunction "2_2") (pintype "passive"))
      (node (ref "C20") (pin "1") (pinfunction "1_1") (pintype "passive"))
      (node (ref "C21") (pin "1") (pinfunction "1_1") (pintype "passive"))
      (node (ref "C23") (pin "2") (pinfunction "2_2") (pintype "passive"))
      (node (ref "C5") (pin "2") (pinfunction "2_2") (pintype "passive"))
      (node (ref "C8") (pin "2") (pinfunction "2_2") (pintype "passive"))
      (node (ref "DBUS1") (pin "3") (pinfunction "3_3") (pintype "passive"))
      (node (ref "L2") (pin "1") (pinfunction "1_1") (pintype "passive"))
      (node (ref "R30") (pin "1") (pinfunction "1_1") (pintype "passive"))
      (node (ref "R32") (pin "1") (pinfunction "1_1") (pintype "passive"))
      (node (ref "R8") (pin "1") (pinfunction "1_1") (pintype "passive"))
      (node (ref "S1") (pin "3") (pinfunction "B1_3") (pintype "passive"))
      (node (ref "STM1") (pin "18") (pinfunction "VSS_1_18") (pintype "passive"))
      (node (ref "STM1") (pin "63") (pinfunction "VSS_2_63") (pintype "passive"))
      (node (ref "U12") (pin "2") (pinfunction "GND_2") (pintype "passive"))
      (node (ref "U8") (pin "2") (pinfunction "GND_2") (pintype "passive"))
    )
    (net (code "40") (name "GND") (class "Default")
      (node (ref "C10") (pin "2") (pinfunction "2_2") (pintype "passive"))
      (node (ref "C11") (pin "1") (pinfunction "1_1") (pintype "passive"))
      (node (ref "C12") (pin "1") (pinfunction "1_1") (pintype "passive"))
      (node (ref "C13") (pin "1") (pinfunction "1_1") (pintype "passive"))
      (node (ref "C14") (pin "1") (pinfunction "1_1") (pintype "passive"))
      (node (ref "C22") (pin "1") (pinfunction "1_1") (pintype "passive"))
      (node (ref "C3") (pin "1") (pinfunction "1_1") (pintype "passive"))
      (node (ref "D1") (pin "1") (pinfunction "A_1") (pintype "passive"))
      (node (ref "D10") (pin "1") (pinfunction "A_1") (pintype "passive"))
      (node (ref "D11") (pin "1") (pinfunction "A_1") (pintype "passive"))
      (node (ref "D13") (pin "2") (pinfunction "K_2") (pintype "passive"))
      (node (ref "D2") (pin "1") (pinfunction "A_1") (pintype "passive"))
      (node (ref "D3") (pin "1") (pinfunction "A_1") (pintype "passive"))
      (node (ref "D4") (pin "1") (pinfunction "A_1") (pintype "passive"))
      (node (ref "D5") (pin "1") (pinfunction "A_1") (pintype "passive"))
      (node (ref "D6") (pin "2") (pinfunction "K_2") (pintype "passive"))
      (node (ref "D7") (pin "1") (pinfunction "A_1") (pintype "passive"))
      (node (ref "D8") (pin "1") (pinfunction "A_1") (pintype "passive"))
      (node (ref "D9") (pin "2") (pinfunction "K_2") (pintype "passive"))
      (node (ref "MOS2") (pin "1") (pinfunction "S_1") (pintype "passive"))
      (node (ref "MOS2") (pin "2") (pinfunction "S_2") (pintype "passive"))
      (node (ref "MOS2") (pin "3") (pinfunction "S_3") (pintype "passive"))
      (node (ref "P14") (pin "5") (pinfunction "5_5") (pintype "passive"))
      (node (ref "P15") (pin "3") (pinfunction "3_3") (pintype "passive"))
      (node (ref "P18") (pin "2") (pinfunction "2_2") (pintype "passive"))
      (node (ref "P19") (pin "2") (pinfunction "2_2") (pintype "passive"))
      (node (ref "P21") (pin "2") (pinfunction "2_2") (pintype "passive"))
      (node (ref "P22") (pin "2") (pinfunction "2_2") (pintype "passive"))
      (node (ref "P28") (pin "1") (pinfunction "1_1") (pintype "passive"))
      (node (ref "P29") (pin "1") (pinfunction "1_1") (pintype "passive"))
      (node (ref "P30") (pin "1") (pinfunction "1_1") (pintype "passive"))
      (node (ref "P31") (pin "1") (pinfunction "1_1") (pintype "passive"))
      (node (ref "Q1") (pin "2") (pinfunction "E_2") (pintype "passive"))
      (node (ref "R13") (pin "1") (pinfunction "TOP_1") (pintype "passive"))
      (node (ref "R30") (pin "2") (pinfunction "2_2") (pintype "passive"))
      (node (ref "R31") (pin "1") (pinfunction "1_1") (pintype "passive"))
      (node (ref "R32") (pin "2") (pinfunction "2_2") (pintype "passive"))
      (node (ref "R9") (pin "2") (pinfunction "2_2") (pintype "passive"))
      (node (ref "SWD1") (pin "3") (pinfunction "3_3") (pintype "passive"))
      (node (ref "U10") (pin "2") (pinfunction "b_2") (pintype "passive"))
      (node (ref "U11") (pin "2") (pinfunction "b_2") (pintype "passive"))
      (node (ref "U13") (pin "2") (pinfunction "b_2") (pintype "passive"))
      (node (ref "U14") (pin "2") (pinfunction "b_2") (pintype "passive"))
      (node (ref "U2") (pin "6") (pinfunction "GND_6") (pintype "power_in"))
      (node (ref "U2") (pin "9") (pinfunction "PAD_9") (pintype "power_in"))
      (node (ref "U3") (pin "2") (pinfunction "b_2") (pintype "passive"))
      (node (ref "U4") (pin "2") (pinfunction "b_2") (pintype "passive"))
      (node (ref "U5") (pin "1") (pinfunction "GND_1") (pintype "passive"))
      (node (ref "U6") (pin "2") (pinfunction "b_2") (pintype "passive"))
      (node (ref "U7") (pin "2") (pinfunction "b_2") (pintype "passive"))
      (node (ref "ZD1") (pin "2") (pinfunction "2_2") (pintype "passive"))
    )
    (net (code "41") (name "GND-BAT") (class "Default")
      (node (ref "C7") (pin "1") (pinfunction "1_1") (pintype "passive"))
      (node (ref "CR1") (pin "1") (pinfunction "11_1") (pintype "passive"))
      (node (ref "CR2") (pin "2") (pinfunction "2_2") (pintype "passive"))
      (node (ref "MOS2") (pin "5") (pinfunction "D_5") (pintype "passive"))
      (node (ref "P1") (pin "2") (pinfunction "-_2") (pintype "passive"))
      (node (ref "P25") (pin "2") (pinfunction "-_2") (pintype "passive"))
      (node (ref "P26") (pin "2") (pinfunction "-_2") (pintype "passive"))
      (node (ref "P4") (pin "2") (pinfunction "-_2") (pintype "passive"))
      (node (ref "P5") (pin "2") (pinfunction "-_2") (pintype "passive"))
      (node (ref "P8") (pin "2") (pinfunction "-_2") (pintype "passive"))
    )
    (net (code "42") (name "Net-(C3-Pad2)") (class "Default")
      (node (ref "C3") (pin "2") (pinfunction "2_2") (pintype "passive"))
      (node (ref "R1") (pin "2") (pinfunction "2_2") (pintype "passive"))
    )
    (net (code "43") (name "Net-(C4-Pad1)") (class "Default")
      (node (ref "C4") (pin "1") (pinfunction "1_1") (pintype "passive"))
      (node (ref "R7") (pin "1") (pinfunction "1_1") (pintype "passive"))
      (node (ref "R9") (pin "1") (pinfunction "1_1") (pintype "passive"))
      (node (ref "U1") (pin "3") (pinfunction "3_3") (pintype "passive"))
    )
    (net (code "44") (name "Net-(C4-Pad2)") (class "Default")
      (node (ref "C4") (pin "2") (pinfunction "2_2") (pintype "passive"))
      (node (ref "R5") (pin "2") (pinfunction "2_2") (pintype "passive"))
      (node (ref "U1") (pin "1") (pinfunction "1_1") (pintype "passive"))
    )
    (net (code "45") (name "Net-(C7-Pad2)") (class "Default")
      (node (ref "C7") (pin "2") (pinfunction "2_2") (pintype "passive"))
      (node (ref "R2") (pin "2") (pinfunction "2_2") (pintype "passive"))
    )
    (net (code "46") (name "Net-(CR2-Pad1)") (class "Default")
      (node (ref "CR2") (pin "1") (pinfunction "1_1") (pintype "passive"))
      (node (ref "R4") (pin "2") (pinfunction "2_2") (pintype "passive"))
      (node (ref "R5") (pin "1") (pinfunction "1_1") (pintype "passive"))
    )
    (net (code "47") (name "Net-(D1-K)") (class "Default")
      (node (ref "C9") (pin "2") (pinfunction "2_2") (pintype "passive"))
      (node (ref "D1") (pin "2") (pinfunction "K_2") (pintype "passive"))
      (node (ref "L1") (pin "1") (pinfunction "1_1") (pintype "passive"))
      (node (ref "U2") (pin "8") (pinfunction "PH_8") (pintype "power_in"))
    )
    (net (code "48") (name "Net-(D2-K)") (class "Default")
      (node (ref "D2") (pin "2") (pinfunction "K_2") (pintype "passive"))
      (node (ref "P2") (pin "1") (pinfunction "1_1") (pintype "passive"))
      (node (ref "U3") (pin "3") (pinfunction "c_3") (pintype "passive"))
    )
    (net (code "49") (name "Net-(D3-K)") (class "Default")
      (node (ref "D3") (pin "2") (pinfunction "K_2") (pintype "passive"))
      (node (ref "P3") (pin "1") (pinfunction "1_1") (pintype "passive"))
      (node (ref "U4") (pin "3") (pinfunction "c_3") (pintype "passive"))
    )
    (net (code "50") (name "Net-(D4-K)") (class "Default")
      (node (ref "D4") (pin "2") (pinfunction "K_2") (pintype "passive"))
      (node (ref "P6") (pin "1") (pinfunction "1_1") (pintype "passive"))
      (node (ref "U6") (pin "3") (pinfunction "c_3") (pintype "passive"))
    )
    (net (code "51") (name "Net-(D5-K)") (class "Default")
      (node (ref "D5") (pin "2") (pinfunction "K_2") (pintype "passive"))
      (node (ref "P7") (pin "1") (pinfunction "1_1") (pintype "passive"))
      (node (ref "U7") (pin "3") (pinfunction "c_3") (pintype "passive"))
    )
    (net (code "52") (name "Net-(D6-A)") (class "Default")
      (node (ref "D6") (pin "1") (pinfunction "A_1") (pintype "passive"))
      (node (ref "R14") (pin "2") (pinfunction "2_2") (pintype "passive"))
    )
    (net (code "53") (name "Net-(D7-K)") (class "Default")
      (node (ref "D7") (pin "2") (pinfunction "K_2") (pintype "passive"))
      (node (ref "P9") (pin "1") (pinfunction "1_1") (pintype "passive"))
      (node (ref "U10") (pin "3") (pinfunction "c_3") (pintype "passive"))
    )
    (net (code "54") (name "Net-(D8-K)") (class "Default")
      (node (ref "D8") (pin "2") (pinfunction "K_2") (pintype "passive"))
      (node (ref "P10") (pin "1") (pinfunction "1_1") (pintype "passive"))
      (node (ref "U11") (pin "3") (pinfunction "c_3") (pintype "passive"))
    )
    (net (code "55") (name "Net-(D9-A)") (class "Default")
      (node (ref "D9") (pin "1") (pinfunction "A_1") (pintype "passive"))
      (node (ref "R22") (pin "2") (pinfunction "2_2") (pintype "passive"))
    )
    (net (code "56") (name "Net-(D10-K)") (class "Default")
      (node (ref "D10") (pin "2") (pinfunction "K_2") (pintype "passive"))
      (node (ref "P11") (pin "1") (pinfunction "1_1") (pintype "passive"))
      (node (ref "U13") (pin "3") (pinfunction "c_3") (pintype "passive"))
    )
    (net (code "57") (name "Net-(D11-K)") (class "Default")
      (node (ref "D11") (pin "2") (pinfunction "K_2") (pintype "passive"))
      (node (ref "P12") (pin "1") (pinfunction "1_1") (pintype "passive"))
      (node (ref "U14") (pin "3") (pinfunction "c_3") (pintype "passive"))
    )
    (net (code "58") (name "Net-(D13-A)") (class "Default")
      (node (ref "D13") (pin "1") (pinfunction "A_1") (pintype "passive"))
      (node (ref "R23") (pin "2") (pinfunction "2_2") (pintype "passive"))
    )
    (net (code "59") (name "Net-(DBUS1-Pad1)") (class "Default")
      (node (ref "DBUS1") (pin "1") (pinfunction "1_1") (pintype "passive"))
      (node (ref "R33") (pin "2") (pinfunction "2_2") (pintype "passive"))
    )
    (net (code "60") (name "Net-(MOS1-2)") (class "Default")
      (node (ref "MOS1") (pin "4") (pinfunction "2_4") (pintype "passive"))
      (node (ref "R7") (pin "2") (pinfunction "2_2") (pintype "passive"))
    )
    (net (code "61") (name "Net-(MOS2-G)") (class "Default")
      (node (ref "MOS2") (pin "4") (pinfunction "G_4") (pintype "passive"))
      (node (ref "R3") (pin "2") (pinfunction "2_2") (pintype "passive"))
      (node (ref "ZD1") (pin "1") (pinfunction "1_1") (pintype "passive"))
    )
    (net (code "62") (name "Net-(Q1-B)") (class "Default")
      (node (ref "Q1") (pin "1") (pinfunction "B_1") (pintype "passive"))
      (node (ref "R33") (pin "1") (pinfunction "1_1") (pintype "passive"))
    )
    (net (code "63") (name "Net-(R10-BOT)") (class "Default")
      (node (ref "R10") (pin "2") (pinfunction "BOT_2") (pintype "passive"))
      (node (ref "R13") (pin "2") (pinfunction "BOT_2") (pintype "passive"))
      (node (ref "U2") (pin "4") (pinfunction "VSNS_4") (pintype "power_in"))
    )
    (net (code "64") (name "Net-(S1-A1)") (class "Default")
      (node (ref "S1") (pin "1") (pinfunction "A1_1") (pintype "passive"))
      (node (ref "STM1") (pin "7") (pinfunction "NRST_7") (pintype "passive"))
    )
    (net (code "65") (name "Net-(S1-A2)") (class "Default")
      (node (ref "C6") (pin "2") (pinfunction "2_2") (pintype "passive"))
      (node (ref "R6") (pin "1") (pinfunction "1_1") (pintype "passive"))
      (node (ref "S1") (pin "2") (pinfunction "A2_2") (pintype "passive"))
    )
    (net (code "66") (name "Net-(S1-B2)") (class "Default")
      (node (ref "C6") (pin "1") (pinfunction "1_1") (pintype "passive"))
      (node (ref "S1") (pin "4") (pinfunction "B2_4") (pintype "passive"))
    )
    (net (code "67") (name "Net-(STM1A-BOOT0)") (class "Default")
      (node (ref "R8") (pin "2") (pinfunction "2_2") (pintype "passive"))
      (node (ref "STM1") (pin "60") (pinfunction "BOOT0_60") (pintype "passive"))
    )
    (net (code "68") (name "Net-(STM1A-OSC_IN)") (class "Default")
      (node (ref "C1") (pin "1") (pinfunction "1_1") (pintype "passive"))
      (node (ref "STM1") (pin "5") (pinfunction "OSC_IN_5") (pintype "passive"))
      (node (ref "XT1") (pin "1") (pinfunction "OSC1_1") (pintype "passive"))
    )
    (net (code "69") (name "Net-(STM1A-OSC_OUT)") (class "Default")
      (node (ref "C2") (pin "1") (pinfunction "1_1") (pintype "passive"))
      (node (ref "STM1") (pin "6") (pinfunction "OSC_OUT_6") (pintype "passive"))
      (node (ref "XT1") (pin "3") (pinfunction "OSC2_3") (pintype "passive"))
    )
    (net (code "70") (name "Net-(STM1A-VCAP_1)") (class "Default")
      (node (ref "C5") (pin "1") (pinfunction "1_1") (pintype "passive"))
      (node (ref "STM1") (pin "31") (pinfunction "VCAP_1_31") (pintype "passive"))
    )
    (net (code "71") (name "Net-(STM1A-VCAP_2)") (class "Default")
      (node (ref "C8") (pin "1") (pinfunction "1_1") (pintype "passive"))
      (node (ref "STM1") (pin "47") (pinfunction "VCAP_2_47") (pintype "passive"))
    )
    (net (code "72") (name "Net-(U2-BOOT)") (class "Default")
      (node (ref "C9") (pin "1") (pinfunction "1_1") (pintype "passive"))
      (node (ref "U2") (pin "1") (pinfunction "BOOT_1") (pintype "power_in"))
    )
    (net (code "73") (name "Net-(U3-e)") (class "Default")
      (node (ref "R11") (pin "2") (pinfunction "2_2") (pintype "passive"))
      (node (ref "U3") (pin "1") (pinfunction "e_1") (pintype "passive"))
    )
    (net (code "74") (name "Net-(U4-e)") (class "Default")
      (node (ref "R12") (pin "2") (pinfunction "2_2") (pintype "passive"))
      (node (ref "U4") (pin "1") (pinfunction "e_1") (pintype "passive"))
    )
    (net (code "75") (name "Net-(U6-e)") (class "Default")
      (node (ref "R15") (pin "2") (pinfunction "2_2") (pintype "passive"))
      (node (ref "U6") (pin "1") (pinfunction "e_1") (pintype "passive"))
    )
    (net (code "76") (name "Net-(U7-e)") (class "Default")
      (node (ref "R16") (pin "2") (pinfunction "2_2") (pintype "passive"))
      (node (ref "U7") (pin "1") (pinfunction "e_1") (pintype "passive"))
    )
    (net (code "77") (name "Net-(U10-e)") (class "Default")
      (node (ref "R19") (pin "2") (pinfunction "2_2") (pintype "passive"))
      (node (ref "U10") (pin "1") (pinfunction "e_1") (pintype "passive"))
    )
    (net (code "78") (name "Net-(U11-e)") (class "Default")
      (node (ref "R20") (pin "2") (pinfunction "2_2") (pintype "passive"))
      (node (ref "U11") (pin "1") (pinfunction "e_1") (pintype "passive"))
    )
    (net (code "79") (name "Net-(U13-e)") (class "Default")
      (node (ref "R25") (pin "2") (pinfunction "2_2") (pintype "passive"))
      (node (ref "U13") (pin "1") (pinfunction "e_1") (pintype "passive"))
    )
    (net (code "80") (name "Net-(U14-e)") (class "Default")
      (node (ref "R26") (pin "2") (pinfunction "2_2") (pintype "passive"))
      (node (ref "U14") (pin "1") (pinfunction "e_1") (pintype "passive"))
    )
    (net (code "81") (name "VCC-3V3") (class "Default")
      (node (ref "C13") (pin "2") (pinfunction "2_2") (pintype "passive"))
      (node (ref "C14") (pin "2") (pinfunction "2_2") (pintype "passive"))
      (node (ref "C15") (pin "1") (pinfunction "1_1") (pintype "passive"))
      (node (ref "C16") (pin "1") (pinfunction "1_1") (pintype "passive"))
      (node (ref "C17") (pin "2") (pinfunction "2_2") (pintype "passive"))
      (node (ref "C18") (pin "2") (pinfunction "2_2") (pintype "passive"))
      (node (ref "C19") (pin "2") (pinfunction "2_2") (pintype "passive"))
      (node (ref "C20") (pin "2") (pinfunction "2_2") (pintype "passive"))
      (node (ref "C21") (pin "2") (pinfunction "2_2") (pintype "passive"))
      (node (ref "C23") (pin "1") (pinfunction "1_1") (pintype "passive"))
      (node (ref "L3") (pin "1") (pinfunction "1_1") (pintype "passive"))
      (node (ref "R14") (pin "1") (pinfunction "1_1") (pintype "passive"))
      (node (ref "R17") (pin "1") (pinfunction "1_1") (pintype "passive"))
      (node (ref "R18") (pin "1") (pinfunction "1_1") (pintype "passive"))
      (node (ref "R29") (pin "1") (pinfunction "1_1") (pintype "passive"))
      (node (ref "R6") (pin "2") (pinfunction "2_2") (pintype "passive"))
      (node (ref "STM1") (pin "1") (pinfunction "VBAT_1") (pintype "passive"))
      (node (ref "STM1") (pin "19") (pinfunction "VDD_1_19") (pintype "passive"))
      (node (ref "STM1") (pin "32") (pinfunction "VDD_2_32") (pintype "passive"))
      (node (ref "STM1") (pin "48") (pinfunction "VDD_3_48") (pintype "passive"))
      (node (ref "STM1") (pin "64") (pinfunction "VDD_4_64") (pintype "passive"))
      (node (ref "SWD1") (pin "4") (pinfunction "4_4") (pintype "passive"))
      (node (ref "U12") (pin "3") (pinfunction "VCC_3") (pintype "passive"))
      (node (ref "U5") (pin "2") (pinfunction "3V3_2") (pintype "passive"))
      (node (ref "U8") (pin "3") (pinfunction "VCC_3") (pintype "passive"))
    )
    (net (code "82") (name "VCC-5V") (class "Default")
      (node (ref "C10") (pin "1") (pinfunction "1_1") (pintype "passive"))
      (node (ref "C11") (pin "2") (pinfunction "2_2") (pintype "passive"))
      (node (ref "C12") (pin "2") (pinfunction "2_2") (pintype "passive"))
      (node (ref "DBUS1") (pin "2") (pinfunction "2_2") (pintype "passive"))
      (node (ref "L1") (pin "2") (pinfunction "2_2") (pintype "passive"))
      (node (ref "P15") (pin "2") (pinfunction "2_2") (pintype "passive"))
      (node (ref "P18") (pin "1") (pinfunction "1_1") (pintype "passive"))
      (node (ref "P19") (pin "1") (pinfunction "1_1") (pintype "passive"))
      (node (ref "P21") (pin "1") (pinfunction "1_1") (pintype "passive"))
      (node (ref "P22") (pin "1") (pinfunction "1_1") (pintype "passive"))
      (node (ref "P28") (pin "3") (pinfunction "3_3") (pintype "passive"))
      (node (ref "P29") (pin "3") (pinfunction "3_3") (pintype "passive"))
      (node (ref "P30") (pin "3") (pinfunction "3_3") (pintype "passive"))
      (node (ref "P31") (pin "3") (pinfunction "3_3") (pintype "passive"))
      (node (ref "R10") (pin "1") (pinfunction "TOP_1") (pintype "passive"))
      (node (ref "U5") (pin "3") (pinfunction "5V_3") (pintype "passive"))
    )
    (net (code "83") (name "VCC-24V") (class "Default")
      (node (ref "MOS1") (pin "5") (pinfunction "1_5") (pintype "passive"))
      (node (ref "MOS1") (pin "6") (pinfunction "4_6") (pintype "passive"))
      (node (ref "MOS1") (pin "7") (pinfunction "5_7") (pintype "passive"))
      (node (ref "MOS1") (pin "8") (pinfunction "6_8") (pintype "passive"))
      (node (ref "P10") (pin "2") (pinfunction "2_2") (pintype "passive"))
      (node (ref "P11") (pin "2") (pinfunction "2_2") (pintype "passive"))
      (node (ref "P12") (pin "2") (pinfunction "2_2") (pintype "passive"))
      (node (ref "P2") (pin "2") (pinfunction "2_2") (pintype "passive"))
      (node (ref "P3") (pin "2") (pinfunction "2_2") (pintype "passive"))
      (node (ref "P6") (pin "2") (pinfunction "2_2") (pintype "passive"))
      (node (ref "P7") (pin "2") (pinfunction "2_2") (pintype "passive"))
      (node (ref "P9") (pin "2") (pinfunction "2_2") (pintype "passive"))
      (node (ref "R1") (pin "1") (pinfunction "1_1") (pintype "passive"))
      (node (ref "U2") (pin "7") (pinfunction "VIN_7") (pintype "power_in"))
    )
    (net (code "84") (name "VCC-A3V3") (class "Default")
      (node (ref "C24") (pin "1") (pinfunction "1_1") (pintype "passive"))
      (node (ref "L3") (pin "2") (pinfunction "2_2") (pintype "passive"))
      (node (ref "STM1") (pin "13") (pinfunction "VDDA_13") (pintype "passive"))
    )
    (net (code "85") (name "VCC-BAT") (class "Default")
      (node (ref "CR1") (pin "2") (pinfunction "12_2") (pintype "passive"))
      (node (ref "MOS1") (pin "1") (pinfunction "3_1") (pintype "passive"))
      (node (ref "MOS1") (pin "2") (pinfunction "7_2") (pintype "passive"))
      (node (ref "MOS1") (pin "3") (pinfunction "8_3") (pintype "passive"))
      (node (ref "P1") (pin "1") (pinfunction "+_1") (pintype "passive"))
      (node (ref "P25") (pin "1") (pinfunction "+_1") (pintype "passive"))
      (node (ref "P26") (pin "1") (pinfunction "+_1") (pintype "passive"))
      (node (ref "P4") (pin "1") (pinfunction "+_1") (pintype "passive"))
      (node (ref "P5") (pin "1") (pinfunction "+_1") (pintype "passive"))
      (node (ref "P8") (pin "1") (pinfunction "+_1") (pintype "passive"))
      (node (ref "R2") (pin "1") (pinfunction "1_1") (pintype "passive"))
      (node (ref "R28") (pin "2") (pinfunction "2_2") (pintype "passive"))
      (node (ref "R3") (pin "1") (pinfunction "1_1") (pintype "passive"))
      (node (ref "R4") (pin "1") (pinfunction "1_1") (pintype "passive"))
      (node (ref "U1") (pin "2") (pinfunction "2_2") (pintype "passive"))
    )
    (net (code "86") (name "unconnected-(M1-Pad0)") (class "Default")
      (node (ref "M1") (pin "0") (pinfunction "0_0") (pintype "passive"))
    )
    (net (code "87") (name "unconnected-(M2-Pad0)") (class "Default")
      (node (ref "M2") (pin "0") (pinfunction "0_0") (pintype "passive"))
    )
    (net (code "88") (name "unconnected-(M3-Pad0)") (class "Default")
      (node (ref "M3") (pin "0") (pinfunction "0_0") (pintype "passive"))
    )
    (net (code "89") (name "unconnected-(M4-Pad0)") (class "Default")
      (node (ref "M4") (pin "0") (pinfunction "0_0") (pintype "passive"))
    )
    (net (code "90") (name "unconnected-(STM1B-PA2-Pad16)") (class "Default")
      (node (ref "STM1") (pin "16") (pinfunction "PA2_16") (pintype "passive"))
    )
    (net (code "91") (name "unconnected-(STM1B-PA8-Pad41)") (class "Default")
      (node (ref "STM1") (pin "41") (pinfunction "PA8_41") (pintype "passive"))
    )
    (net (code "92") (name "unconnected-(STM1B-PA15-Pad50)") (class "Default")
      (node (ref "STM1") (pin "50") (pinfunction "PA15_50") (pintype "passive"))
    )
    (net (code "93") (name "unconnected-(STM1B-PB3-Pad55)") (class "Default")
      (node (ref "STM1") (pin "55") (pinfunction "PB3_55") (pintype "passive"))
    )
    (net (code "94") (name "unconnected-(STM1B-PB7-Pad59)") (class "Default")
      (node (ref "STM1") (pin "59") (pinfunction "PB7_59") (pintype "passive"))
    )
    (net (code "95") (name "unconnected-(STM1B-PB8-Pad61)") (class "Default")
      (node (ref "STM1") (pin "61") (pinfunction "PB8_61") (pintype "passive"))
    )
    (net (code "96") (name "unconnected-(STM1B-PB9-Pad62)") (class "Default")
      (node (ref "STM1") (pin "62") (pinfunction "PB9_62") (pintype "passive"))
    )
    (net (code "97") (name "unconnected-(STM1B-PB15-Pad36)") (class "Default")
      (node (ref "STM1") (pin "36") (pinfunction "PB15_36") (pintype "passive"))
    )
    (net (code "98") (name "unconnected-(STM1B-PC0-Pad8)") (class "Default")
      (node (ref "STM1") (pin "8") (pinfunction "PC0_8") (pintype "passive"))
    )
    (net (code "99") (name "unconnected-(STM1B-PC1-Pad9)") (class "Default")
      (node (ref "STM1") (pin "9") (pinfunction "PC1_9") (pintype "passive"))
    )
    (net (code "100") (name "unconnected-(STM1B-PC2-Pad10)") (class "Default")
      (node (ref "STM1") (pin "10") (pinfunction "PC2_10") (pintype "passive"))
    )
    (net (code "101") (name "unconnected-(STM1B-PC9-Pad40)") (class "Default")
      (node (ref "STM1") (pin "40") (pinfunction "PC9_40") (pintype "passive"))
    )
    (net (code "102") (name "unconnected-(STM1B-PC10-Pad51)") (class "Default")
      (node (ref "STM1") (pin "51") (pinfunction "PC10_51") (pintype "passive"))
    )
    (net (code "103") (name "unconnected-(STM1B-PC13-Pad2)") (class "Default")
      (node (ref "STM1") (pin "2") (pinfunction "PC13_2") (pintype "passive"))
    )
    (net (code "104") (name "unconnected-(STM1B-PC14-Pad3)") (class "Default")
      (node (ref "STM1") (pin "3") (pinfunction "PC14_3") (pintype "passive"))
    )
    (net (code "105") (name "unconnected-(STM1B-PC15-Pad4)") (class "Default")
      (node (ref "STM1") (pin "4") (pinfunction "PC15_4") (pintype "passive"))
    )
    (net (code "106") (name "unconnected-(U2-ENA-Pad5)") (class "Default")
      (node (ref "U2") (pin "5") (pinfunction "ENA_5") (pintype "power_in+no_connect"))
    )
    (net (code "107") (name "unconnected-(U2-NC-Pad2)") (class "Default")
      (node (ref "U2") (pin "2") (pinfunction "NC_2") (pintype "power_in+no_connect"))
    )
    (net (code "108") (name "unconnected-(U2-NC-Pad3)") (class "Default")
      (node (ref "U2") (pin "3") (pinfunction "NC_3") (pintype "power_in+no_connect"))
    )
    (net (code "109") (name "unconnected-(U8-RS-Pad8)") (class "Default")
      (node (ref "U8") (pin "8") (pinfunction "RS_8") (pintype "passive"))
    )
    (net (code "110") (name "unconnected-(U8-VREF-Pad5)") (class "Default")
      (node (ref "U8") (pin "5") (pinfunction "VREF_5") (pintype "passive"))
    )
    (net (code "111") (name "unconnected-(U12-RS-Pad8)") (class "Default")
      (node (ref "U12") (pin "8") (pinfunction "RS_8") (pintype "passive"))
    )
    (net (code "112") (name "unconnected-(U12-VREF-Pad5)") (class "Default")
      (node (ref "U12") (pin "5") (pinfunction "VREF_5") (pintype "passive"))
    )
  )
)
